# Ultra-Mega-PS-PowerSupplies-V1_00.net
KiCad netlist of a schematic drawn in Altium Designer
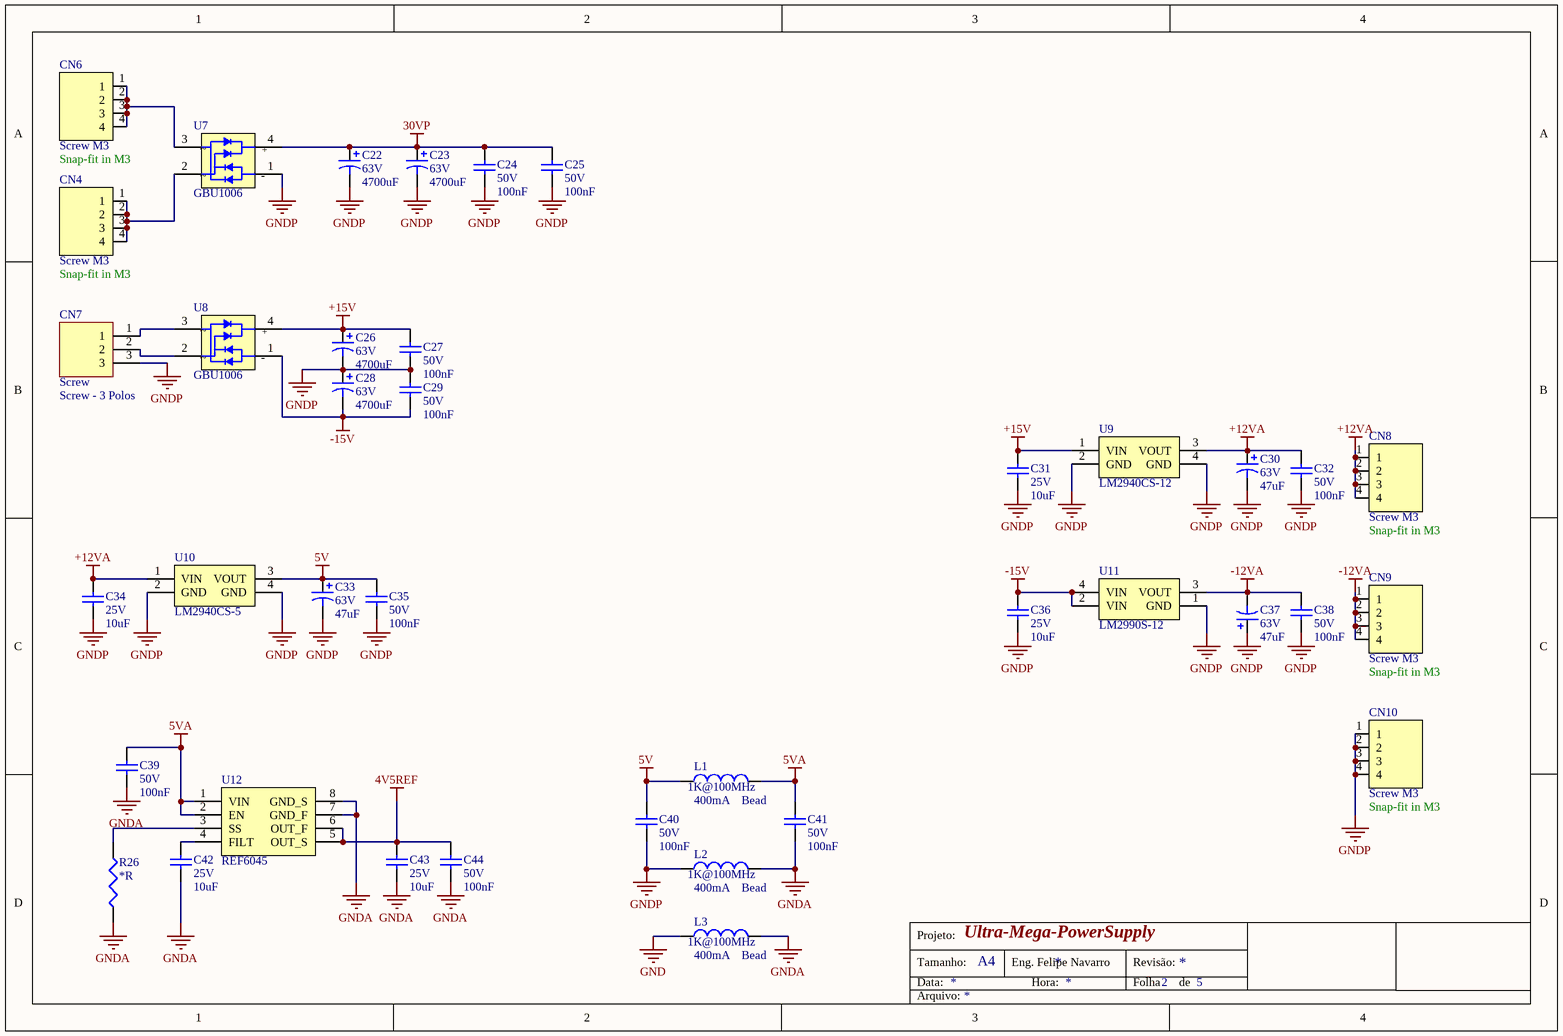
[diagram p0: Ultra-Mega-PS-PowerSupplies-V1.00.SchDoc]

(export (version "E")
  (design (tool "Eeschema 10.0.6"))
  (components
    (comp (ref "C22")
      (value "4700uF")
      (footprint "CAP NICHICON 25x40")
      (description "Polarized Capacitor (Radial)")
      (fields (field (name "TENSÃO") "63V") (field (name "Comment") "Capacitor Eletrolítico"))
      (libsource (lib "NavarroCAP") (part "PCap 4700uF 63V"))
    )
    (comp (ref "C23")
      (value "4700uF")
      (footprint "CAP NICHICON 25x40")
      (description "Polarized Capacitor (Radial)")
      (fields (field (name "TENSÃO") "63V") (field (name "Comment") "Capacitor Eletrolítico"))
      (libsource (lib "NavarroCAP") (part "PCap 4700uF 63V"))
    )
    (comp (ref "C24")
      (value "100nF")
      (footprint "CC0603")
      (description "Capacitor (Semiconductor SIM Model)")
      (fields (field (name "TENSÃO") "50V") (field (name "Comment") "Capacitor Cerâmico"))
      (libsource (lib "NavarroCAP") (part "Cap 100nF 50V 0603 X7R"))
    )
    (comp (ref "C25")
      (value "100nF")
      (footprint "CC0603")
      (description "Capacitor (Semiconductor SIM Model)")
      (fields (field (name "TENSÃO") "50V") (field (name "Comment") "Capacitor Cerâmico"))
      (libsource (lib "NavarroCAP") (part "Cap 100nF 50V 0603 X7R"))
    )
    (comp (ref "C26")
      (value "4700uF")
      (footprint "CAP NICHICON 25x40")
      (description "Polarized Capacitor (Radial)")
      (fields (field (name "TENSÃO") "63V") (field (name "Comment") "Capacitor Eletrolítico"))
      (libsource (lib "NavarroCAP") (part "PCap 4700uF 63V"))
    )
    (comp (ref "C27")
      (value "100nF")
      (footprint "CC0603")
      (description "Capacitor (Semiconductor SIM Model)")
      (fields (field (name "TENSÃO") "50V") (field (name "Comment") "Capacitor Cerâmico"))
      (libsource (lib "NavarroCAP") (part "Cap 100nF 50V 0603 X7R"))
    )
    (comp (ref "C28")
      (value "4700uF")
      (footprint "CAP NICHICON 25x40")
      (description "Polarized Capacitor (Radial)")
      (fields (field (name "TENSÃO") "63V") (field (name "Comment") "Capacitor Eletrolítico"))
      (libsource (lib "NavarroCAP") (part "PCap 4700uF 63V"))
    )
    (comp (ref "C29")
      (value "100nF")
      (footprint "CC0603")
      (description "Capacitor (Semiconductor SIM Model)")
      (fields (field (name "TENSÃO") "50V") (field (name "Comment") "Capacitor Cerâmico"))
      (libsource (lib "NavarroCAP") (part "Cap 100nF 50V 0603 X7R"))
    )
    (comp (ref "C30")
      (value "47uF")
      (footprint "CPOLRAD6X12")
      (description "Polarized Capacitor (Radial)")
      (fields (field (name "TENSÃO") "63V") (field (name "Comment") "Capacitor Eletrolítico"))
      (libsource (lib "NavarroCAP") (part "PCap 47uF 63V 6d.x12h."))
    )
    (comp (ref "C31")
      (value "10uF")
      (footprint "CC0805")
      (description "Capacitor (Semiconductor SIM Model)")
      (fields (field (name "TENSÃO") "25V") (field (name "Comment") "Capacitor Cerâmico"))
      (libsource (lib "NavarroCAP") (part "Cap 10uF 25V 0805 X5R"))
    )
    (comp (ref "C32")
      (value "100nF")
      (footprint "CC0603")
      (description "Capacitor (Semiconductor SIM Model)")
      (fields (field (name "TENSÃO") "50V") (field (name "Comment") "Capacitor Cerâmico"))
      (libsource (lib "NavarroCAP") (part "Cap 100nF 50V 0603 X7R"))
    )
    (comp (ref "C33")
      (value "47uF")
      (footprint "CPOLRAD6X12")
      (description "Polarized Capacitor (Radial)")
      (fields (field (name "TENSÃO") "63V") (field (name "Comment") "Capacitor Eletrolítico"))
      (libsource (lib "NavarroCAP") (part "PCap 47uF 63V 6d.x12h."))
    )
    (comp (ref "C34")
      (value "10uF")
      (footprint "CC0805")
      (description "Capacitor (Semiconductor SIM Model)")
      (fields (field (name "TENSÃO") "25V") (field (name "Comment") "Capacitor Cerâmico"))
      (libsource (lib "NavarroCAP") (part "Cap 10uF 25V 0805 X5R"))
    )
    (comp (ref "C35")
      (value "100nF")
      (footprint "CC0603")
      (description "Capacitor (Semiconductor SIM Model)")
      (fields (field (name "TENSÃO") "50V") (field (name "Comment") "Capacitor Cerâmico"))
      (libsource (lib "NavarroCAP") (part "Cap 100nF 50V 0603 X7R"))
    )
    (comp (ref "C36")
      (value "10uF")
      (footprint "CC0805")
      (description "Capacitor (Semiconductor SIM Model)")
      (fields (field (name "TENSÃO") "25V") (field (name "Comment") "Capacitor Cerâmico"))
      (libsource (lib "NavarroCAP") (part "Cap 10uF 25V 0805 X5R"))
    )
    (comp (ref "C37")
      (value "47uF")
      (footprint "CPOLRAD6X12")
      (description "Polarized Capacitor (Radial)")
      (fields (field (name "TENSÃO") "63V") (field (name "Comment") "Capacitor Eletrolítico"))
      (libsource (lib "NavarroCAP") (part "PCap 47uF 63V 6d.x12h."))
    )
    (comp (ref "C38")
      (value "100nF")
      (footprint "CC0603")
      (description "Capacitor (Semiconductor SIM Model)")
      (fields (field (name "TENSÃO") "50V") (field (name "Comment") "Capacitor Cerâmico"))
      (libsource (lib "NavarroCAP") (part "Cap 100nF 50V 0603 X7R"))
    )
    (comp (ref "C39")
      (value "100nF")
      (footprint "CC0603")
      (description "Capacitor (Semiconductor SIM Model)")
      (fields (field (name "TENSÃO") "50V") (field (name "Comment") "Capacitor Cerâmico"))
      (libsource (lib "NavarroCAP") (part "Cap 100nF 50V 0603 X7R"))
    )
    (comp (ref "C40")
      (value "100nF")
      (footprint "CC0603")
      (description "Capacitor (Semiconductor SIM Model)")
      (fields (field (name "TENSÃO") "50V") (field (name "Comment") "Capacitor Cerâmico"))
      (libsource (lib "NavarroCAP") (part "Cap 100nF 50V 0603 X7R"))
    )
    (comp (ref "C41")
      (value "100nF")
      (footprint "CC0603")
      (description "Capacitor (Semiconductor SIM Model)")
      (fields (field (name "TENSÃO") "50V") (field (name "Comment") "Capacitor Cerâmico"))
      (libsource (lib "NavarroCAP") (part "Cap 100nF 50V 0603 X7R"))
    )
    (comp (ref "C42")
      (value "10uF")
      (footprint "CC0805")
      (description "Capacitor (Semiconductor SIM Model)")
      (fields (field (name "TENSÃO") "25V") (field (name "Comment") "Capacitor Cerâmico"))
      (libsource (lib "NavarroCAP") (part "Cap 10uF 25V 0805 X5R"))
    )
    (comp (ref "C43")
      (value "10uF")
      (footprint "CC0805")
      (description "Capacitor (Semiconductor SIM Model)")
      (fields (field (name "TENSÃO") "25V") (field (name "Comment") "Capacitor Cerâmico"))
      (libsource (lib "NavarroCAP") (part "Cap 10uF 25V 0805 X5R"))
    )
    (comp (ref "C44")
      (value "100nF")
      (footprint "CC0603")
      (description "Capacitor (Semiconductor SIM Model)")
      (fields (field (name "TENSÃO") "50V") (field (name "Comment") "Capacitor Cerâmico"))
      (libsource (lib "NavarroCAP") (part "Cap 100nF 50V 0603 X7R"))
    )
    (comp (ref "CN4")
      (value "Screw M3")
      (footprint "CONN_MASSA-M3")
      (description "TERM PCB SNAP-IN VERT M3 THREAD")
      (fields (field (name "ALTIUM_VALUE") "Snap-fit in M3"))
      (libsource (lib "NavarroCON") (part "Screw Snap-Fit M3"))
    )
    (comp (ref "CN6")
      (value "Screw M3")
      (footprint "CONN_MASSA-M3")
      (description "TERM PCB SNAP-IN VERT M3 THREAD")
      (fields (field (name "ALTIUM_VALUE") "Snap-fit in M3"))
      (libsource (lib "NavarroCON") (part "Screw Snap-Fit M3"))
    )
    (comp (ref "CN7")
      (value "Screw")
      (footprint "CONN SCREW-3N P5.08")
      (description "Conector Screw Block")
      (fields (field (name "ALTIUM_VALUE") "Screw - 3 Polos"))
      (libsource (lib "NavarroCON") (part "Screw-3 125V 6A P2.54mm"))
    )
    (comp (ref "CN8")
      (value "Screw M3")
      (footprint "CONN_MASSA-M3")
      (description "TERM PCB SNAP-IN VERT M3 THREAD")
      (fields (field (name "ALTIUM_VALUE") "Snap-fit in M3"))
      (libsource (lib "") (part "Screw Snap-Fit M3_1"))
    )
    (comp (ref "CN9")
      (value "Screw M3")
      (footprint "CONN_MASSA-M3")
      (description "TERM PCB SNAP-IN VERT M3 THREAD")
      (fields (field (name "ALTIUM_VALUE") "Snap-fit in M3"))
      (libsource (lib "") (part "Screw Snap-Fit M3_1"))
    )
    (comp (ref "CN10")
      (value "Screw M3")
      (footprint "CONN_MASSA-M3")
      (description "TERM PCB SNAP-IN VERT M3 THREAD")
      (fields (field (name "ALTIUM_VALUE") "Snap-fit in M3"))
      (libsource (lib "") (part "Screw Snap-Fit M3_1"))
    )
    (comp (ref "L1")
      (value "Bead")
      (footprint "CC0603")
      (fields (field (name "CORRENTE") "400mA") (field (name "ALTIUM_VALUE") "1K@100MHz"))
      (libsource (lib "NavarroIND") (part "Bd 1K@100MHz 0603 400mA"))
    )
    (comp (ref "L2")
      (value "Bead")
      (footprint "CC0603")
      (fields (field (name "CORRENTE") "400mA") (field (name "ALTIUM_VALUE") "1K@100MHz"))
      (libsource (lib "NavarroIND") (part "Bd 1K@100MHz 0603 400mA"))
    )
    (comp (ref "L3")
      (value "Bead")
      (footprint "CC0603")
      (fields (field (name "CORRENTE") "400mA") (field (name "ALTIUM_VALUE") "1K@100MHz"))
      (libsource (lib "NavarroIND") (part "Bd 1K@100MHz 0603 400mA"))
    )
    (comp (ref "R26")
      (value "*R")
      (footprint "CC0603")
      (description "Resistor")
      (libsource (lib "NavarroRES") (part "Res - $Val $% $Footprint $Pot"))
    )
    (comp (ref "U7")
      (value "GBU1006")
      (footprint "GBU1006")
      (description "600V 10A")
      (libsource (lib "NavarroSEMI") (part "BRG GBU1006 600V 10A"))
    )
    (comp (ref "U8")
      (value "GBU1006")
      (footprint "GBU1006")
      (description "600V 10A")
      (libsource (lib "NavarroSEMI") (part "BRG GBU1006 600V 10A"))
    )
    (comp (ref "U9")
      (value "LM2940CS-12")
      (footprint "TO263-4N")
      (description "Regulador Linear 15V Positivo")
      (libsource (lib "Navarro") (part "LM2940-15"))
    )
    (comp (ref "U10")
      (value "LM2940CS-5")
      (footprint "TO263-4N")
      (description "Regulador Linear 15V Positivo")
      (libsource (lib "Navarro") (part "LM2940-15"))
    )
    (comp (ref "U11")
      (value "LM2990S-12")
      (footprint "TO263-4N")
      (description "Regulador Linear 15V Negativo")
      (libsource (lib "Navarro") (part "LM2990-15"))
    )
    (comp (ref "U12")
      (value "REF6045")
      (footprint "VFSOP-8N")
      (description "REF60xx High-Precision Voltage Reference With Integrated ADC Drive Buffer")
      (libsource (lib "Navarro") (part "REF6050"))
    )
  )
  (nets
    (net (code "1") (name "+12VA") (class "Default")
      (node (ref "C30") (pin "1") (pinfunction "1_1") (pintype "passive"))
      (node (ref "C32") (pin "2") (pinfunction "2_2") (pintype "passive"))
      (node (ref "C34") (pin "2") (pinfunction "2_2") (pintype "passive"))
      (node (ref "CN8") (pin "1") (pinfunction "1_1") (pintype "power_in"))
      (node (ref "CN8") (pin "2") (pinfunction "2_2") (pintype "power_in"))
      (node (ref "CN8") (pin "3") (pinfunction "3_3") (pintype "power_in"))
      (node (ref "CN8") (pin "4") (pinfunction "4_4") (pintype "power_in"))
      (node (ref "U10") (pin "1") (pinfunction "VIN_1") (pintype "power_in"))
      (node (ref "U9") (pin "3") (pinfunction "VOUT_3") (pintype "power_in"))
    )
    (net (code "2") (name "+15V") (class "Default")
      (node (ref "C26") (pin "2") (pinfunction "2_2") (pintype "passive"))
      (node (ref "C27") (pin "2") (pinfunction "2_2") (pintype "passive"))
      (node (ref "C31") (pin "2") (pinfunction "2_2") (pintype "passive"))
      (node (ref "U8") (pin "4") (pinfunction "G_4") (pintype "passive"))
      (node (ref "U9") (pin "1") (pinfunction "VIN_1") (pintype "power_in"))
    )
    (net (code "3") (name "-12VA") (class "Default")
      (node (ref "C37") (pin "2") (pinfunction "2_2") (pintype "passive"))
      (node (ref "C38") (pin "2") (pinfunction "2_2") (pintype "passive"))
      (node (ref "CN9") (pin "1") (pinfunction "1_1") (pintype "power_in"))
      (node (ref "CN9") (pin "2") (pinfunction "2_2") (pintype "power_in"))
      (node (ref "CN9") (pin "3") (pinfunction "3_3") (pintype "power_in"))
      (node (ref "CN9") (pin "4") (pinfunction "4_4") (pintype "power_in"))
      (node (ref "U11") (pin "3") (pinfunction "VOUT_3") (pintype "power_in"))
    )
    (net (code "4") (name "-15V") (class "Default")
      (node (ref "C28") (pin "1") (pinfunction "1_1") (pintype "passive"))
      (node (ref "C29") (pin "1") (pinfunction "1_1") (pintype "passive"))
      (node (ref "C36") (pin "2") (pinfunction "2_2") (pintype "passive"))
      (node (ref "U11") (pin "2") (pinfunction "VIN_2") (pintype "power_in"))
      (node (ref "U11") (pin "4") (pinfunction "VIN_4") (pintype "power_in"))
      (node (ref "U8") (pin "1") (pinfunction "S_1") (pintype "passive"))
    )
    (net (code "5") (name "4V5REF") (class "Default")
      (node (ref "C43") (pin "2") (pinfunction "2_2") (pintype "passive"))
      (node (ref "C44") (pin "2") (pinfunction "2_2") (pintype "passive"))
      (node (ref "U12") (pin "5") (pinfunction "OUT_S_5") (pintype "passive"))
      (node (ref "U12") (pin "6") (pinfunction "OUT_F_6") (pintype "passive"))
    )
    (net (code "6") (name "5V") (class "Default")
      (node (ref "C33") (pin "1") (pinfunction "1_1") (pintype "passive"))
      (node (ref "C35") (pin "2") (pinfunction "2_2") (pintype "passive"))
      (node (ref "C40") (pin "2") (pinfunction "2_2") (pintype "passive"))
      (node (ref "L1") (pin "1") (pinfunction "1_1") (pintype "passive"))
      (node (ref "U10") (pin "3") (pinfunction "VOUT_3") (pintype "power_in"))
    )
    (net (code "7") (name "5VA") (class "Default")
      (node (ref "C39") (pin "2") (pinfunction "2_2") (pintype "passive"))
      (node (ref "C41") (pin "2") (pinfunction "2_2") (pintype "passive"))
      (node (ref "L1") (pin "2") (pinfunction "2_2") (pintype "passive"))
      (node (ref "U12") (pin "1") (pinfunction "VIN_1") (pintype "power_in"))
      (node (ref "U12") (pin "2") (pinfunction "EN_2") (pintype "passive"))
    )
    (net (code "8") (name "30VP") (class "Default")
      (node (ref "C22") (pin "2") (pinfunction "2_2") (pintype "passive"))
      (node (ref "C23") (pin "2") (pinfunction "2_2") (pintype "passive"))
      (node (ref "C24") (pin "2") (pinfunction "2_2") (pintype "passive"))
      (node (ref "C25") (pin "2") (pinfunction "2_2") (pintype "passive"))
      (node (ref "U7") (pin "4") (pinfunction "G_4") (pintype "passive"))
    )
    (net (code "9") (name "GND") (class "Default")
      (node (ref "L3") (pin "1") (pinfunction "1_1") (pintype "passive"))
    )
    (net (code "10") (name "GNDA") (class "Default")
      (node (ref "C39") (pin "1") (pinfunction "1_1") (pintype "passive"))
      (node (ref "C41") (pin "1") (pinfunction "1_1") (pintype "passive"))
      (node (ref "C42") (pin "1") (pinfunction "1_1") (pintype "passive"))
      (node (ref "C43") (pin "1") (pinfunction "1_1") (pintype "passive"))
      (node (ref "C44") (pin "1") (pinfunction "1_1") (pintype "passive"))
      (node (ref "L2") (pin "2") (pinfunction "2_2") (pintype "passive"))
      (node (ref "L3") (pin "2") (pinfunction "2_2") (pintype "passive"))
      (node (ref "R26") (pin "1") (pinfunction "1_1") (pintype "passive"))
      (node (ref "U12") (pin "7") (pinfunction "GND_F_7") (pintype "power_in"))
      (node (ref "U12") (pin "8") (pinfunction "GND_S_8") (pintype "power_in"))
    )
    (net (code "11") (name "GNDP") (class "Default")
      (node (ref "C22") (pin "1") (pinfunction "1_1") (pintype "passive"))
      (node (ref "C23") (pin "1") (pinfunction "1_1") (pintype "passive"))
      (node (ref "C24") (pin "1") (pinfunction "1_1") (pintype "passive"))
      (node (ref "C25") (pin "1") (pinfunction "1_1") (pintype "passive"))
      (node (ref "C26") (pin "1") (pinfunction "1_1") (pintype "passive"))
      (node (ref "C27") (pin "1") (pinfunction "1_1") (pintype "passive"))
      (node (ref "C28") (pin "2") (pinfunction "2_2") (pintype "passive"))
      (node (ref "C29") (pin "2") (pinfunction "2_2") (pintype "passive"))
      (node (ref "C30") (pin "2") (pinfunction "2_2") (pintype "passive"))
      (node (ref "C31") (pin "1") (pinfunction "1_1") (pintype "passive"))
      (node (ref "C32") (pin "1") (pinfunction "1_1") (pintype "passive"))
      (node (ref "C33") (pin "2") (pinfunction "2_2") (pintype "passive"))
      (node (ref "C34") (pin "1") (pinfunction "1_1") (pintype "passive"))
      (node (ref "C35") (pin "1") (pinfunction "1_1") (pintype "passive"))
      (node (ref "C36") (pin "1") (pinfunction "1_1") (pintype "passive"))
      (node (ref "C37") (pin "1") (pinfunction "1_1") (pintype "passive"))
      (node (ref "C38") (pin "1") (pinfunction "1_1") (pintype "passive"))
      (node (ref "C40") (pin "1") (pinfunction "1_1") (pintype "passive"))
      (node (ref "CN10") (pin "1") (pinfunction "1_1") (pintype "power_in"))
      (node (ref "CN10") (pin "2") (pinfunction "2_2") (pintype "power_in"))
      (node (ref "CN10") (pin "3") (pinfunction "3_3") (pintype "power_in"))
      (node (ref "CN10") (pin "4") (pinfunction "4_4") (pintype "power_in"))
      (node (ref "CN7") (pin "3") (pinfunction "3_3") (pintype "passive"))
      (node (ref "L2") (pin "1") (pinfunction "1_1") (pintype "passive"))
      (node (ref "U10") (pin "2") (pinfunction "GND_2") (pintype "power_in"))
      (node (ref "U10") (pin "4") (pinfunction "GND_4") (pintype "power_in"))
      (node (ref "U11") (pin "1") (pinfunction "GND_1") (pintype "power_in"))
      (node (ref "U7") (pin "1") (pinfunction "S_1") (pintype "passive"))
      (node (ref "U9") (pin "2") (pinfunction "GND_2") (pintype "power_in"))
      (node (ref "U9") (pin "4") (pinfunction "GND_4") (pintype "power_in"))
    )
    (net (code "12") (name "Net-(CN4-Pad1)") (class "Default")
      (node (ref "CN4") (pin "1") (pinfunction "1_1") (pintype "power_in"))
      (node (ref "CN4") (pin "2") (pinfunction "2_2") (pintype "power_in"))
      (node (ref "CN4") (pin "3") (pinfunction "3_3") (pintype "power_in"))
      (node (ref "CN4") (pin "4") (pinfunction "4_4") (pintype "power_in"))
      (node (ref "U7") (pin "2") (pinfunction "AC_2") (pintype "passive"))
    )
    (net (code "13") (name "Net-(CN6-Pad1)") (class "Default")
      (node (ref "CN6") (pin "1") (pinfunction "1_1") (pintype "power_in"))
      (node (ref "CN6") (pin "2") (pinfunction "2_2") (pintype "power_in"))
      (node (ref "CN6") (pin "3") (pinfunction "3_3") (pintype "power_in"))
      (node (ref "CN6") (pin "4") (pinfunction "4_4") (pintype "power_in"))
      (node (ref "U7") (pin "3") (pinfunction "AC_3") (pintype "passive"))
    )
    (net (code "14") (name "Net-(CN7-Pad1)") (class "Default")
      (node (ref "CN7") (pin "1") (pinfunction "1_1") (pintype "passive"))
      (node (ref "U8") (pin "3") (pinfunction "AC_3") (pintype "passive"))
    )
    (net (code "15") (name "Net-(CN7-Pad2)") (class "Default")
      (node (ref "CN7") (pin "2") (pinfunction "2_2") (pintype "passive"))
      (node (ref "U8") (pin "2") (pinfunction "AC_2") (pintype "passive"))
    )
    (net (code "16") (name "Net-(U12-FILT)") (class "Default")
      (node (ref "C42") (pin "2") (pinfunction "2_2") (pintype "passive"))
      (node (ref "U12") (pin "4") (pinfunction "FILT_4") (pintype "passive"))
    )
    (net (code "17") (name "Net-(U12-SS)") (class "Default")
      (node (ref "R26") (pin "2") (pinfunction "2_2") (pintype "passive"))
      (node (ref "U12") (pin "3") (pinfunction "SS_3") (pintype "passive"))
    )
  )
)
